# eight-button-sheild.net
KiCad netlist of a schematic drawn in EAGLE
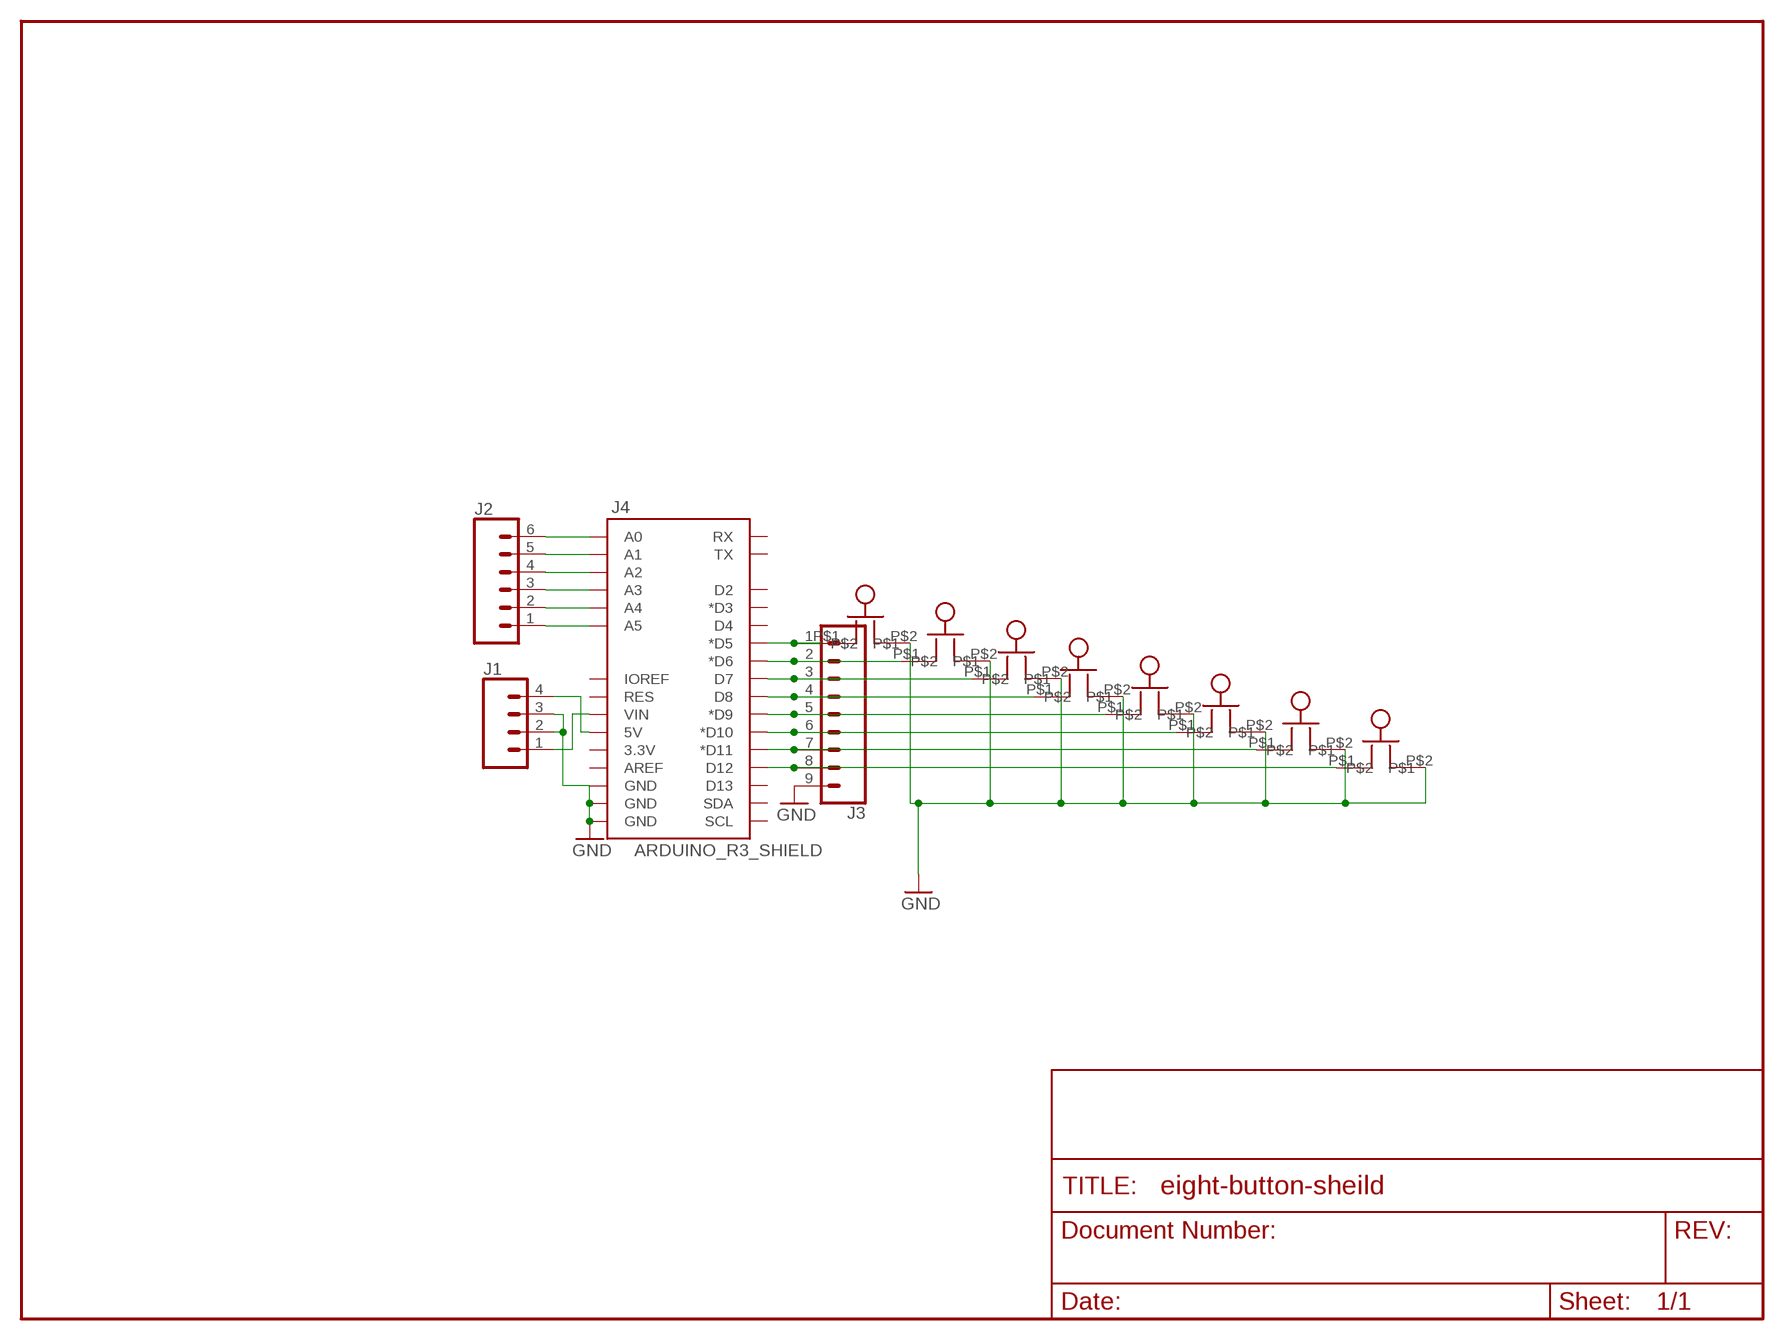
[diagram p0: schematic, sheet 1]

(export (version "E")
  (design (tool "Eeschema 10.0.6"))
  (components
    (comp (ref "J1")
      (value "CONN_04")
      (footprint "eagle-import:1X04")
      (libsource (lib "eagle-import") (part "CONN_04"))
    )
    (comp (ref "J2")
      (value "CONN_06SILK_FEMALE_PTH")
      (footprint "eagle-import:1X06")
      (libsource (lib "eagle-import") (part "CONN_06SILK_FEMALE_PTH"))
    )
    (comp (ref "J3")
      (value "CONN_09")
      (footprint "eagle-import:1X09")
      (libsource (lib "eagle-import") (part "CONN_09"))
    )
    (comp (ref "J4")
      (value "ARDUINO_R3_SHIELD")
      (footprint "eagle-import:UNO_R3_SHIELD")
      (libsource (lib "eagle-import") (part "ARDUINO_R3_SHIELD"))
    )
    (comp (ref "SW1")
      (value "BUTTON")
      (footprint "eagle-import:BUTTON")
      (libsource (lib "eagle-import") (part "BUTTON"))
    )
    (comp (ref "SW2")
      (value "BUTTON")
      (footprint "eagle-import:BUTTON")
      (libsource (lib "eagle-import") (part "BUTTON"))
    )
    (comp (ref "SW3")
      (value "BUTTON")
      (footprint "eagle-import:BUTTON")
      (libsource (lib "eagle-import") (part "BUTTON"))
    )
    (comp (ref "SW4")
      (value "BUTTON")
      (footprint "eagle-import:BUTTON")
      (libsource (lib "eagle-import") (part "BUTTON"))
    )
    (comp (ref "SW5")
      (value "BUTTON")
      (footprint "eagle-import:BUTTON")
      (libsource (lib "eagle-import") (part "BUTTON"))
    )
    (comp (ref "SW6")
      (value "BUTTON")
      (footprint "eagle-import:BUTTON")
      (libsource (lib "eagle-import") (part "BUTTON"))
    )
    (comp (ref "SW7")
      (value "BUTTON")
      (footprint "eagle-import:BUTTON")
      (libsource (lib "eagle-import") (part "BUTTON"))
    )
    (comp (ref "SW8")
      (value "BUTTON")
      (footprint "eagle-import:BUTTON")
      (libsource (lib "eagle-import") (part "BUTTON"))
    )
  )
  (nets
    (net (code "1") (name "GND") (class "Default")
      (node (ref "J1") (pin "2") (pinfunction "2_2") (pintype "passive"))
      (node (ref "J1") (pin "3") (pinfunction "3_3") (pintype "passive"))
      (node (ref "J3") (pin "9") (pinfunction "9_9") (pintype "passive"))
      (node (ref "J4") (pin "GND@0") (pinfunction "GND_GND@0") (pintype "bidirectional"))
      (node (ref "J4") (pin "GND@1") (pinfunction "GND_GND@1") (pintype "bidirectional"))
      (node (ref "J4") (pin "GND@2") (pinfunction "GND_GND@2") (pintype "bidirectional"))
      (node (ref "SW1") (pin "P$2") (pinfunction "P$2_P$2") (pintype "bidirectional"))
      (node (ref "SW2") (pin "P$2") (pinfunction "P$2_P$2") (pintype "bidirectional"))
      (node (ref "SW3") (pin "P$2") (pinfunction "P$2_P$2") (pintype "bidirectional"))
      (node (ref "SW4") (pin "P$2") (pinfunction "P$2_P$2") (pintype "bidirectional"))
      (node (ref "SW5") (pin "P$2") (pinfunction "P$2_P$2") (pintype "bidirectional"))
      (node (ref "SW6") (pin "P$2") (pinfunction "P$2_P$2") (pintype "bidirectional"))
      (node (ref "SW7") (pin "P$2") (pinfunction "P$2_P$2") (pintype "bidirectional"))
      (node (ref "SW8") (pin "P$2") (pinfunction "P$2_P$2") (pintype "bidirectional"))
    )
    (net (code "2") (name "Net-(J1-Pad1)") (class "Default")
      (node (ref "J1") (pin "1") (pinfunction "1_1") (pintype "passive"))
      (node (ref "J4") (pin "VIN") (pinfunction "VIN_VIN") (pintype "bidirectional"))
    )
    (net (code "3") (name "Net-(J1-Pad4)") (class "Default")
      (node (ref "J1") (pin "4") (pinfunction "4_4") (pintype "passive"))
      (node (ref "J4") (pin "5V") (pinfunction "5V_5V") (pintype "bidirectional"))
    )
    (net (code "4") (name "Net-(J2-Pad1)") (class "Default")
      (node (ref "J2") (pin "1") (pinfunction "1_1") (pintype "passive"))
      (node (ref "J4") (pin "A5") (pinfunction "A5_A5") (pintype "bidirectional"))
    )
    (net (code "5") (name "Net-(J2-Pad2)") (class "Default")
      (node (ref "J2") (pin "2") (pinfunction "2_2") (pintype "passive"))
      (node (ref "J4") (pin "A4") (pinfunction "A4_A4") (pintype "bidirectional"))
    )
    (net (code "6") (name "Net-(J2-Pad3)") (class "Default")
      (node (ref "J2") (pin "3") (pinfunction "3_3") (pintype "passive"))
      (node (ref "J4") (pin "A3") (pinfunction "A3_A3") (pintype "bidirectional"))
    )
    (net (code "7") (name "Net-(J2-Pad4)") (class "Default")
      (node (ref "J2") (pin "4") (pinfunction "4_4") (pintype "passive"))
      (node (ref "J4") (pin "A2") (pinfunction "A2_A2") (pintype "bidirectional"))
    )
    (net (code "8") (name "Net-(J2-Pad5)") (class "Default")
      (node (ref "J2") (pin "5") (pinfunction "5_5") (pintype "passive"))
      (node (ref "J4") (pin "A1") (pinfunction "A1_A1") (pintype "bidirectional"))
    )
    (net (code "9") (name "Net-(J2-Pad6)") (class "Default")
      (node (ref "J2") (pin "6") (pinfunction "6_6") (pintype "passive"))
      (node (ref "J4") (pin "A0") (pinfunction "A0_A0") (pintype "bidirectional"))
    )
    (net (code "10") (name "Net-(J3-Pad3)") (class "Default")
      (node (ref "J3") (pin "3") (pinfunction "3_3") (pintype "passive"))
      (node (ref "J4") (pin "D7") (pinfunction "D7_D7") (pintype "bidirectional"))
      (node (ref "SW3") (pin "P$1") (pinfunction "P$1_P$1") (pintype "bidirectional"))
    )
    (net (code "11") (name "Net-(J3-Pad4)") (class "Default")
      (node (ref "J3") (pin "4") (pinfunction "4_4") (pintype "passive"))
      (node (ref "J4") (pin "D8") (pinfunction "D8_D8") (pintype "bidirectional"))
      (node (ref "SW4") (pin "P$1") (pinfunction "P$1_P$1") (pintype "bidirectional"))
    )
    (net (code "12") (name "Net-(J3-Pad8)") (class "Default")
      (node (ref "J3") (pin "8") (pinfunction "8_8") (pintype "passive"))
      (node (ref "J4") (pin "D12") (pinfunction "D12_D12") (pintype "bidirectional"))
      (node (ref "SW8") (pin "P$1") (pinfunction "P$1_P$1") (pintype "bidirectional"))
    )
    (net (code "13") (name "Net-(J4-*D5)") (class "Default")
      (node (ref "J3") (pin "1") (pinfunction "1_1") (pintype "passive"))
      (node (ref "J4") (pin "D5") (pinfunction "*D5_D5") (pintype "bidirectional"))
      (node (ref "SW1") (pin "P$1") (pinfunction "P$1_P$1") (pintype "bidirectional"))
    )
    (net (code "14") (name "Net-(J4-*D6)") (class "Default")
      (node (ref "J3") (pin "2") (pinfunction "2_2") (pintype "passive"))
      (node (ref "J4") (pin "D6") (pinfunction "*D6_D6") (pintype "bidirectional"))
      (node (ref "SW2") (pin "P$1") (pinfunction "P$1_P$1") (pintype "bidirectional"))
    )
    (net (code "15") (name "Net-(J4-*D9)") (class "Default")
      (node (ref "J3") (pin "5") (pinfunction "5_5") (pintype "passive"))
      (node (ref "J4") (pin "D9") (pinfunction "*D9_D9") (pintype "bidirectional"))
      (node (ref "SW5") (pin "P$1") (pinfunction "P$1_P$1") (pintype "bidirectional"))
    )
    (net (code "16") (name "Net-(J4-*D10)") (class "Default")
      (node (ref "J3") (pin "6") (pinfunction "6_6") (pintype "passive"))
      (node (ref "J4") (pin "D10") (pinfunction "*D10_D10") (pintype "bidirectional"))
      (node (ref "SW6") (pin "P$1") (pinfunction "P$1_P$1") (pintype "bidirectional"))
    )
    (net (code "17") (name "Net-(J4-*D11)") (class "Default")
      (node (ref "J3") (pin "7") (pinfunction "7_7") (pintype "passive"))
      (node (ref "J4") (pin "D11") (pinfunction "*D11_D11") (pintype "bidirectional"))
      (node (ref "SW7") (pin "P$1") (pinfunction "P$1_P$1") (pintype "bidirectional"))
    )
    (net (code "18") (name "unconnected-(J4-*D3-PadD3)") (class "Default")
      (node (ref "J4") (pin "D3") (pinfunction "*D3_D3") (pintype "bidirectional"))
    )
    (net (code "19") (name "unconnected-(J4-Pad3.3V)") (class "Default")
      (node (ref "J4") (pin "3.3V") (pinfunction "3.3V_3.3V") (pintype "bidirectional"))
    )
    (net (code "20") (name "unconnected-(J4-PadAREF)") (class "Default")
      (node (ref "J4") (pin "AREF") (pinfunction "AREF_AREF") (pintype "bidirectional"))
    )
    (net (code "21") (name "unconnected-(J4-PadD2)") (class "Default")
      (node (ref "J4") (pin "D2") (pinfunction "D2_D2") (pintype "bidirectional"))
    )
    (net (code "22") (name "unconnected-(J4-PadD4)") (class "Default")
      (node (ref "J4") (pin "D4") (pinfunction "D4_D4") (pintype "bidirectional"))
    )
    (net (code "23") (name "unconnected-(J4-PadD13)") (class "Default")
      (node (ref "J4") (pin "D13") (pinfunction "D13_D13") (pintype "bidirectional"))
    )
    (net (code "24") (name "unconnected-(J4-PadIOREF)") (class "Default")
      (node (ref "J4") (pin "IOREF") (pinfunction "IOREF_IOREF") (pintype "bidirectional"))
    )
    (net (code "25") (name "unconnected-(J4-PadRES)") (class "Default")
      (node (ref "J4") (pin "RES") (pinfunction "RES_RES") (pintype "bidirectional"))
    )
    (net (code "26") (name "unconnected-(J4-PadRX)") (class "Default")
      (node (ref "J4") (pin "RX") (pinfunction "RX_RX") (pintype "bidirectional"))
    )
    (net (code "27") (name "unconnected-(J4-PadSCL)") (class "Default")
      (node (ref "J4") (pin "SCL") (pinfunction "SCL_SCL") (pintype "bidirectional"))
    )
    (net (code "28") (name "unconnected-(J4-PadSDA)") (class "Default")
      (node (ref "J4") (pin "SDA") (pinfunction "SDA_SDA") (pintype "bidirectional"))
    )
    (net (code "29") (name "unconnected-(J4-PadTX)") (class "Default")
      (node (ref "J4") (pin "TX") (pinfunction "TX_TX") (pintype "bidirectional"))
    )
  )
)
